# 02_Power.net
KiCad netlist of a schematic drawn in Altium Designer
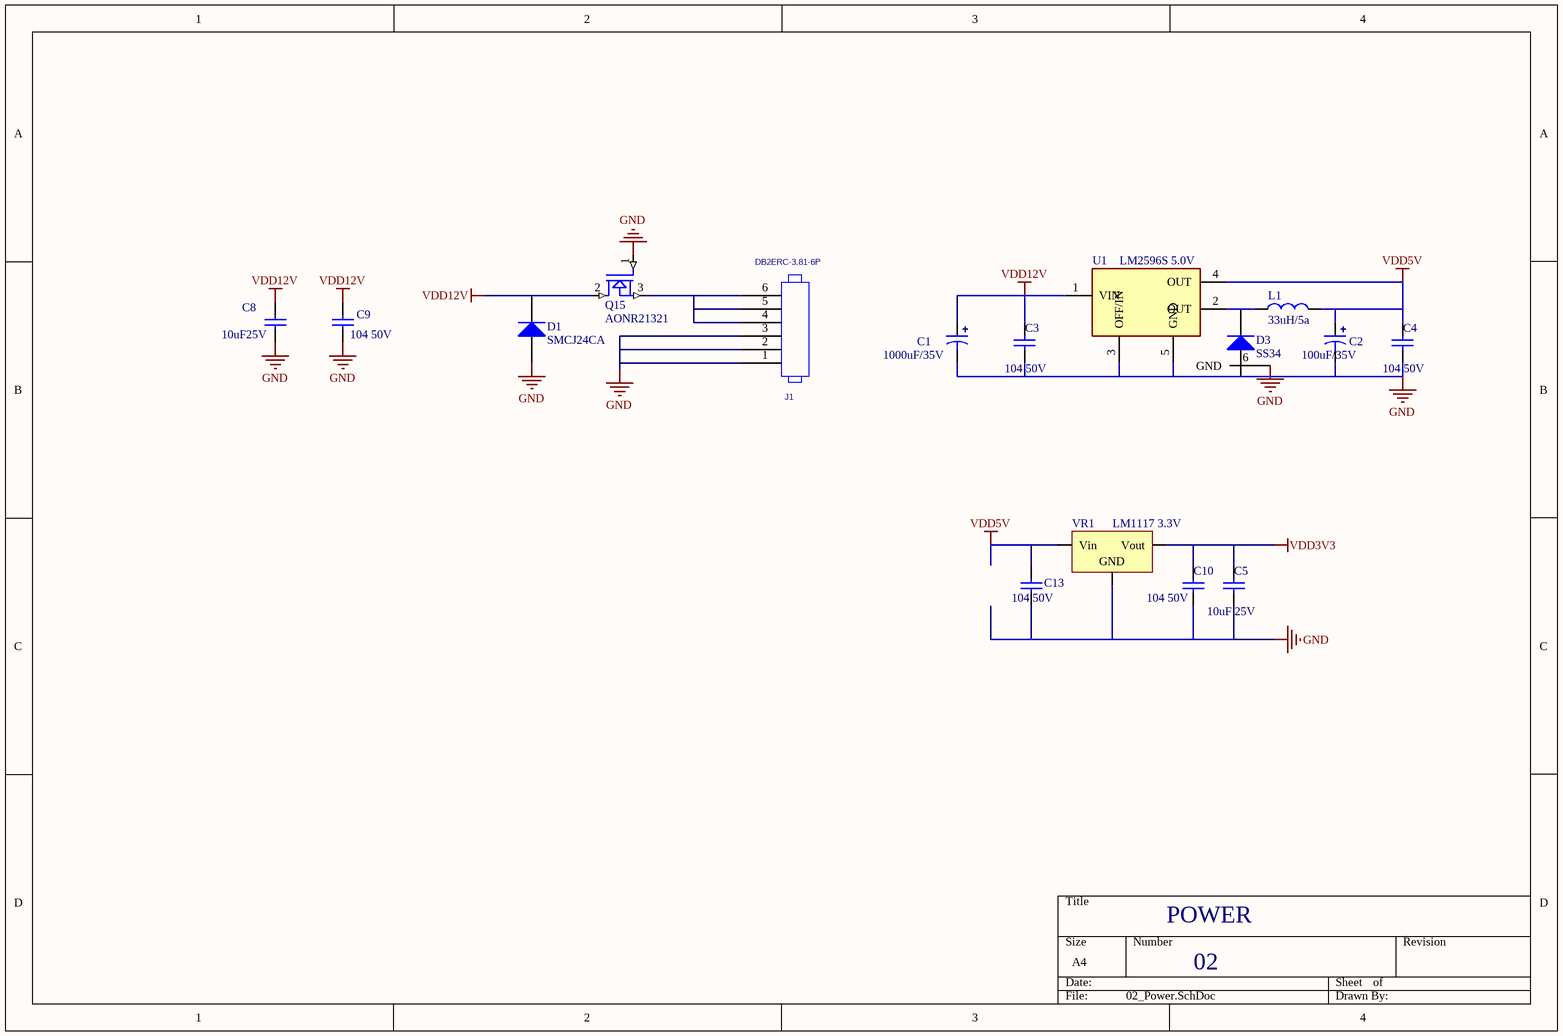
[diagram p0: 02_Power.SchDoc]

(export (version "E")
  (design (tool "Eeschema 10.0.6"))
  (components
    (comp (ref "C1")
      (value "1000uF/35V")
      (footprint "10*16")
      (description "电解电容")
      (libsource (lib "XiaoyI") (part "CAP2"))
    )
    (comp (ref "C2")
      (value "100uF/35V")
      (footprint "6*8")
      (description "电解电容")
      (libsource (lib "XiaoyI") (part "CAP2"))
    )
    (comp (ref "C3")
      (value "104 50V")
      (footprint "SMD-0603C")
      (description "贴片电容 10%")
      (libsource (lib "XiaoyI") (part "CAP4"))
    )
    (comp (ref "C4")
      (value "104 50V")
      (footprint "SMD-0603C")
      (description "贴片电容 10%")
      (libsource (lib "XiaoyI") (part "CAP4"))
    )
    (comp (ref "C5")
      (value "10uF 25V")
      (footprint "SMD-0805C")
      (description "贴片电容 20%")
      (libsource (lib "XiaoyI") (part "CAP4"))
    )
    (comp (ref "C8")
      (value "10uF25V")
      (footprint "SMD-0805C")
      (description "贴片电容 10%")
      (libsource (lib "XiaoyI") (part "CAP4"))
    )
    (comp (ref "C9")
      (value "104 50V")
      (footprint "SMD-0603C")
      (description "贴片电容 10%")
      (libsource (lib "XiaoyI") (part "CAP4"))
    )
    (comp (ref "C10")
      (value "104 50V")
      (footprint "SMD-0603C")
      (description "贴片电容 10%")
      (libsource (lib "XiaoyI") (part "CAP4"))
    )
    (comp (ref "C13")
      (value "104 50V")
      (footprint "SMD-0603C")
      (description "贴片电容 10%")
      (libsource (lib "XiaoyI") (part "CAP4"))
    )
    (comp (ref "D1")
      (value "SMCJ24CA")
      (footprint "Pcblib_20110825:SMC")
      (libsource (lib "Sch_library") (part "DIODE"))
    )
    (comp (ref "D3") (value "SS34") (footprint "SMA") (libsource (lib "Sch_library") (part "DIODE")))
    (comp (ref "J1")
      (value "DB2ERC-3.81-6P")
      (footprint "DB2ERC-3P81-6P")
      (fields (field (name "Comment") "HEADER_6"))
      (libsource (lib "liujingtao_V1.0") (part "HEADER_6"))
    )
    (comp (ref "L1") (value "33uH/5a") (footprint "CDRH-127") (libsource (lib "Sch_library") (part "IND")))
    (comp (ref "Q15")
      (value "AONR21321")
      (footprint "DFN3*3-8")
      (description "MOSFET N")
      (libsource (lib "XiaoyI") (part "MOSFET N"))
    )
    (comp (ref "U1")
      (value "LM2596S 5.0V")
      (footprint "TO-263-5")
      (libsource (lib "Sch_library") (part "LM2596"))
    )
    (comp (ref "VR1")
      (value "LM1117 3.3V")
      (footprint "SOT223")
      (description "三端稳压器")
      (libsource (lib "XiaoyI") (part "LM1117"))
    )
  )
  (nets
    (net (code "1") (name "GND") (class "Default")
      (node (ref "C1") (pin "2") (pinfunction "2_2") (pintype "passive"))
      (node (ref "C10") (pin "1") (pinfunction "1_1") (pintype "passive"))
      (node (ref "C13") (pin "1") (pinfunction "1_1") (pintype "passive"))
      (node (ref "C2") (pin "2") (pinfunction "2_2") (pintype "passive"))
      (node (ref "C3") (pin "1") (pinfunction "1_1") (pintype "passive"))
      (node (ref "C4") (pin "1") (pinfunction "1_1") (pintype "passive"))
      (node (ref "C5") (pin "1") (pinfunction "1_1") (pintype "passive"))
      (node (ref "C8") (pin "1") (pinfunction "1_1") (pintype "passive"))
      (node (ref "C9") (pin "1") (pinfunction "1_1") (pintype "passive"))
      (node (ref "D1") (pin "1") (pinfunction "A_1") (pintype "passive"))
      (node (ref "D3") (pin "1") (pinfunction "A_1") (pintype "passive"))
      (node (ref "J1") (pin "1") (pinfunction "1_1") (pintype "passive"))
      (node (ref "J1") (pin "2") (pinfunction "2_2") (pintype "passive"))
      (node (ref "J1") (pin "3") (pinfunction "3_3") (pintype "passive"))
      (node (ref "Q15") (pin "1") (pinfunction "G_1") (pintype "input"))
      (node (ref "U1") (pin "3") (pinfunction "OFF/IN_3") (pintype "passive"))
      (node (ref "U1") (pin "5") (pinfunction "GND_5") (pintype "passive"))
      (node (ref "U1") (pin "6") (pinfunction "GND_6") (pintype "passive"))
      (node (ref "VR1") (pin "1") (pinfunction "GND_1") (pintype "passive"))
    )
    (net (code "2") (name "Net-(D3-K)") (class "Default")
      (node (ref "D3") (pin "2") (pinfunction "K_2") (pintype "passive"))
      (node (ref "L1") (pin "1") (pinfunction "1_1") (pintype "passive"))
      (node (ref "U1") (pin "2") (pinfunction "OUT_2") (pintype "passive"))
    )
    (net (code "3") (name "Net-(Q15-S)") (class "Default")
      (node (ref "J1") (pin "4") (pinfunction "4_4") (pintype "passive"))
      (node (ref "J1") (pin "5") (pinfunction "5_5") (pintype "passive"))
      (node (ref "J1") (pin "6") (pinfunction "6_6") (pintype "passive"))
      (node (ref "Q15") (pin "3") (pinfunction "S_3") (pintype "output"))
    )
    (net (code "4") (name "VDD3V3") (class "Default")
      (node (ref "C10") (pin "2") (pinfunction "2_2") (pintype "passive"))
      (node (ref "C5") (pin "2") (pinfunction "2_2") (pintype "passive"))
      (node (ref "VR1") (pin "2") (pinfunction "Vout_2") (pintype "passive"))
    )
    (net (code "5") (name "VDD5V") (class "Default")
      (node (ref "C13") (pin "2") (pinfunction "2_2") (pintype "passive"))
      (node (ref "C2") (pin "1") (pinfunction "1_1") (pintype "passive"))
      (node (ref "C4") (pin "2") (pinfunction "2_2") (pintype "passive"))
      (node (ref "L1") (pin "2") (pinfunction "2_2") (pintype "passive"))
      (node (ref "U1") (pin "4") (pinfunction "OUT_4") (pintype "passive"))
      (node (ref "VR1") (pin "3") (pinfunction "Vin_3") (pintype "passive"))
    )
    (net (code "6") (name "VDD12V") (class "Default")
      (node (ref "C1") (pin "1") (pinfunction "1_1") (pintype "passive"))
      (node (ref "C3") (pin "2") (pinfunction "2_2") (pintype "passive"))
      (node (ref "C8") (pin "2") (pinfunction "2_2") (pintype "passive"))
      (node (ref "C9") (pin "2") (pinfunction "2_2") (pintype "passive"))
      (node (ref "D1") (pin "2") (pinfunction "K_2") (pintype "passive"))
      (node (ref "Q15") (pin "2") (pinfunction "D_2") (pintype "input"))
      (node (ref "U1") (pin "1") (pinfunction "VIN_1") (pintype "passive"))
    )
  )
)
